# Sheet1.net
KiCad netlist of a schematic drawn in Altium Designer
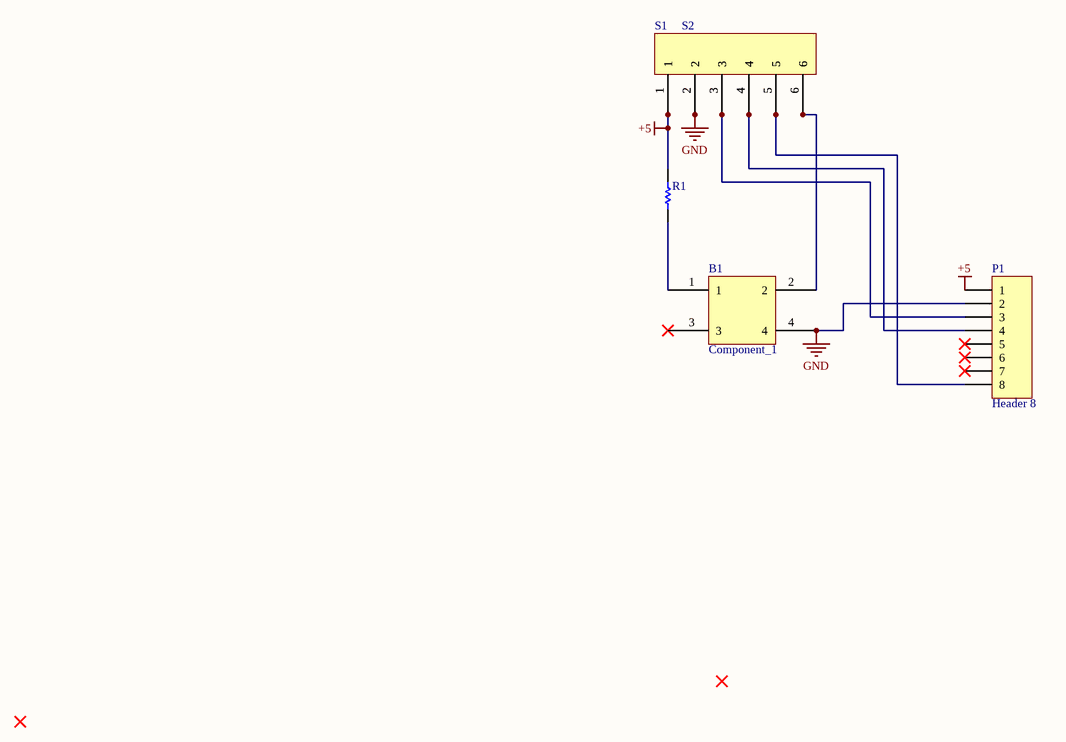
[diagram p0: Sheet1.SchDoc]

(export (version "E")
  (design (tool "Eeschema 10.0.6"))
  (components
    (comp (ref "B1")
      (value "Component_1")
      (footprint "PCBComponent_1")
      (libsource (lib "button") (part "Component_1"))
    )
    (comp (ref "P1")
      (value "Header 8")
      (footprint "HDR1X8")
      (description "Header, 8-Pin")
      (fields (field (name "PUBLISHER") "Altium Limited"))
      (libsource (lib "Miscellaneous Connectors") (part "Header 8"))
    )
    (comp (ref "R1")
      (value "~")
      (footprint "OMTE-RES7X2.5-2")
      (fields
        (field (name "TOLERANCE") "±5%")
        (field (name "PARTNUMBER") "OD103JE")
        (field (name "MANUFACTURER") "Ohmite")
      )
      (libsource (lib "Altium Content Vault") (part "RES-2"))
    )
    (comp (ref "S1")
      (value "~")
      (footprint "PCBComponent_1")
      (libsource (lib "solder_pads") (part "Component_1"))
    )
    (comp (ref "S2")
      (value "~")
      (footprint "PCBComponent_1")
      (libsource (lib "solder_pads") (part "Component_1"))
    )
  )
  (nets
    (net (code "1") (name "+5") (class "Default")
      (node (ref "P1") (pin "1") (pinfunction "1_1") (pintype "passive"))
      (node (ref "R1") (pin "2") (pinfunction "2_2") (pintype "passive"))
      (node (ref "S1") (pin "1") (pinfunction "1_1") (pintype "passive"))
      (node (ref "S2") (pin "1") (pinfunction "1_1") (pintype "passive"))
    )
    (net (code "2") (name "GND") (class "Default")
      (node (ref "B1") (pin "4") (pinfunction "4_4") (pintype "passive"))
      (node (ref "P1") (pin "2") (pinfunction "2_2") (pintype "passive"))
      (node (ref "S1") (pin "2") (pinfunction "2_2") (pintype "passive"))
      (node (ref "S2") (pin "2") (pinfunction "2_2") (pintype "passive"))
    )
    (net (code "3") (name "Net-(B1-Pad1)") (class "Default")
      (node (ref "B1") (pin "1") (pinfunction "1_1") (pintype "passive"))
      (node (ref "R1") (pin "1") (pinfunction "1_1") (pintype "passive"))
    )
    (net (code "4") (name "Net-(B1-Pad2)") (class "Default")
      (node (ref "B1") (pin "2") (pinfunction "2_2") (pintype "passive"))
      (node (ref "S1") (pin "6") (pinfunction "6_6") (pintype "passive"))
      (node (ref "S2") (pin "6") (pinfunction "6_6") (pintype "passive"))
    )
    (net (code "5") (name "Net-(P1-Pad3)") (class "Default")
      (node (ref "P1") (pin "3") (pinfunction "3_3") (pintype "passive"))
      (node (ref "S1") (pin "3") (pinfunction "3_3") (pintype "passive"))
      (node (ref "S2") (pin "3") (pinfunction "3_3") (pintype "passive"))
    )
    (net (code "6") (name "Net-(P1-Pad4)") (class "Default")
      (node (ref "P1") (pin "4") (pinfunction "4_4") (pintype "passive"))
      (node (ref "S1") (pin "4") (pinfunction "4_4") (pintype "passive"))
      (node (ref "S2") (pin "4") (pinfunction "4_4") (pintype "passive"))
    )
    (net (code "7") (name "Net-(P1-Pad8)") (class "Default")
      (node (ref "P1") (pin "8") (pinfunction "8_8") (pintype "passive"))
      (node (ref "S1") (pin "5") (pinfunction "5_5") (pintype "passive"))
      (node (ref "S2") (pin "5") (pinfunction "5_5") (pintype "passive"))
    )
    (net (code "8") (name "unconnected-(B1-Pad3)") (class "Default")
      (node (ref "B1") (pin "3") (pinfunction "3_3") (pintype "passive+no_connect"))
    )
    (net (code "9") (name "unconnected-(P1-Pad5)") (class "Default")
      (node (ref "P1") (pin "5") (pinfunction "5_5") (pintype "passive+no_connect"))
    )
    (net (code "10") (name "unconnected-(P1-Pad6)") (class "Default")
      (node (ref "P1") (pin "6") (pinfunction "6_6") (pintype "passive+no_connect"))
    )
    (net (code "11") (name "unconnected-(P1-Pad7)") (class "Default")
      (node (ref "P1") (pin "7") (pinfunction "7_7") (pintype "passive+no_connect"))
    )
  )
)
